# SVS.net
KiCad netlist of a schematic drawn in Altium Designer
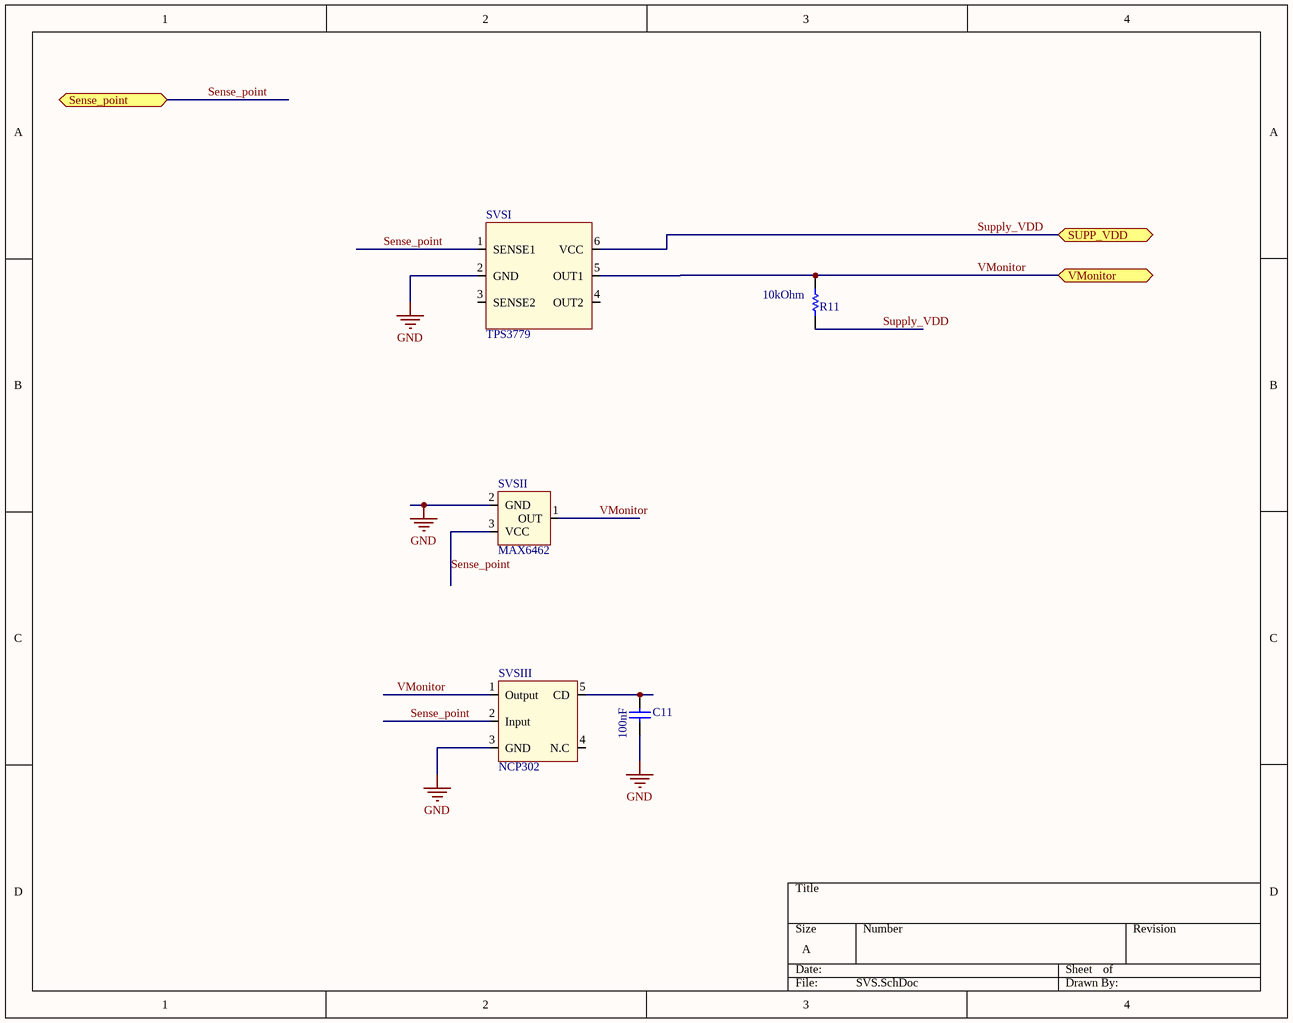
[diagram p0: SVS.SchDoc]

(export (version "E")
  (design (tool "Eeschema 10.0.6"))
  (components
    (comp (ref "C11")
      (value "100nF")
      (footprint "CAPC0402(1005)60_N")
      (description "CAP 1uF 4V ±10% 0402 (1005 Metric) Thickness 0.6mm SMD")
      (fields (field (name "TOLERANCE") "±10%") (field (name "Comment") "CAP 1uF 4V 0402(1005)"))
      (libsource (lib "Altium Content Vault") (part "CMP-1034-02111-1"))
    )
    (comp (ref "R11")
      (value "10kOhm")
      (footprint "RESC0805(2012)_M")
      (description "5R1 0.125W 5% 0805 (2012 Metric)  SMD")
      (fields (field (name "POWER") "0.125 W") (field (name "TOLERANCE") "5 %"))
      (libsource (lib "Altium Content Vault") (part "CMP-1013-00019-1"))
    )
    (comp (ref "SVSI")
      (value "TPS3779")
      (footprint "TPS3779")
      (libsource (lib "Basic_components_hrishi") (part "TPS3779"))
    )
    (comp (ref "SVSII")
      (value "MAX6462")
      (footprint "MAX6462")
      (libsource (lib "Basic_components_hrishi") (part "MAX6462"))
    )
    (comp (ref "SVSIII")
      (value "NCP302")
      (footprint "NCP302")
      (libsource (lib "Basic_components_hrishi") (part "NCP302"))
    )
  )
  (nets
    (net (code "1") (name "/Sense_point") (class "Default")
      (node (ref "SVSI") (pin "1") (pinfunction "SENSE1_1") (pintype "passive"))
      (node (ref "SVSII") (pin "3") (pinfunction "VCC_3") (pintype "passive"))
      (node (ref "SVSIII") (pin "2") (pinfunction "Input_2") (pintype "passive"))
    )
    (net (code "2") (name "/Supply_VDD") (class "Default")
      (node (ref "R11") (pin "1") (pinfunction "1_1") (pintype "passive"))
      (node (ref "SVSI") (pin "6") (pinfunction "VCC_6") (pintype "passive"))
    )
    (net (code "3") (name "/VMonitor") (class "Default")
      (node (ref "R11") (pin "2") (pinfunction "2_2") (pintype "passive"))
      (node (ref "SVSI") (pin "5") (pinfunction "OUT1_5") (pintype "passive"))
      (node (ref "SVSII") (pin "1") (pinfunction "OUT_1") (pintype "passive"))
      (node (ref "SVSIII") (pin "1") (pinfunction "Output_1") (pintype "passive"))
    )
    (net (code "4") (name "GND") (class "Default")
      (node (ref "C11") (pin "1") (pinfunction "1_1") (pintype "passive"))
      (node (ref "SVSI") (pin "2") (pinfunction "GND_2") (pintype "passive"))
      (node (ref "SVSII") (pin "2") (pinfunction "GND_2") (pintype "passive"))
      (node (ref "SVSIII") (pin "3") (pinfunction "GND_3") (pintype "passive"))
    )
    (net (code "5") (name "Net-(SVSIII-CD)") (class "Default")
      (node (ref "C11") (pin "2") (pinfunction "2_2") (pintype "passive"))
      (node (ref "SVSIII") (pin "5") (pinfunction "CD_5") (pintype "passive"))
    )
    (net (code "6") (name "unconnected-(SVSI-OUT2-Pad4)") (class "Default")
      (node (ref "SVSI") (pin "4") (pinfunction "OUT2_4") (pintype "passive"))
    )
    (net (code "7") (name "unconnected-(SVSI-SENSE2-Pad3)") (class "Default")
      (node (ref "SVSI") (pin "3") (pinfunction "SENSE2_3") (pintype "passive"))
    )
    (net (code "8") (name "unconnected-(SVSIII-N.C-Pad4)") (class "Default")
      (node (ref "SVSIII") (pin "4") (pinfunction "N.C_4") (pintype "passive"))
    )
  )
)
